# CNC-PowerSwitch-2016-v0_96.net
KiCad netlist of a schematic drawn in EAGLE
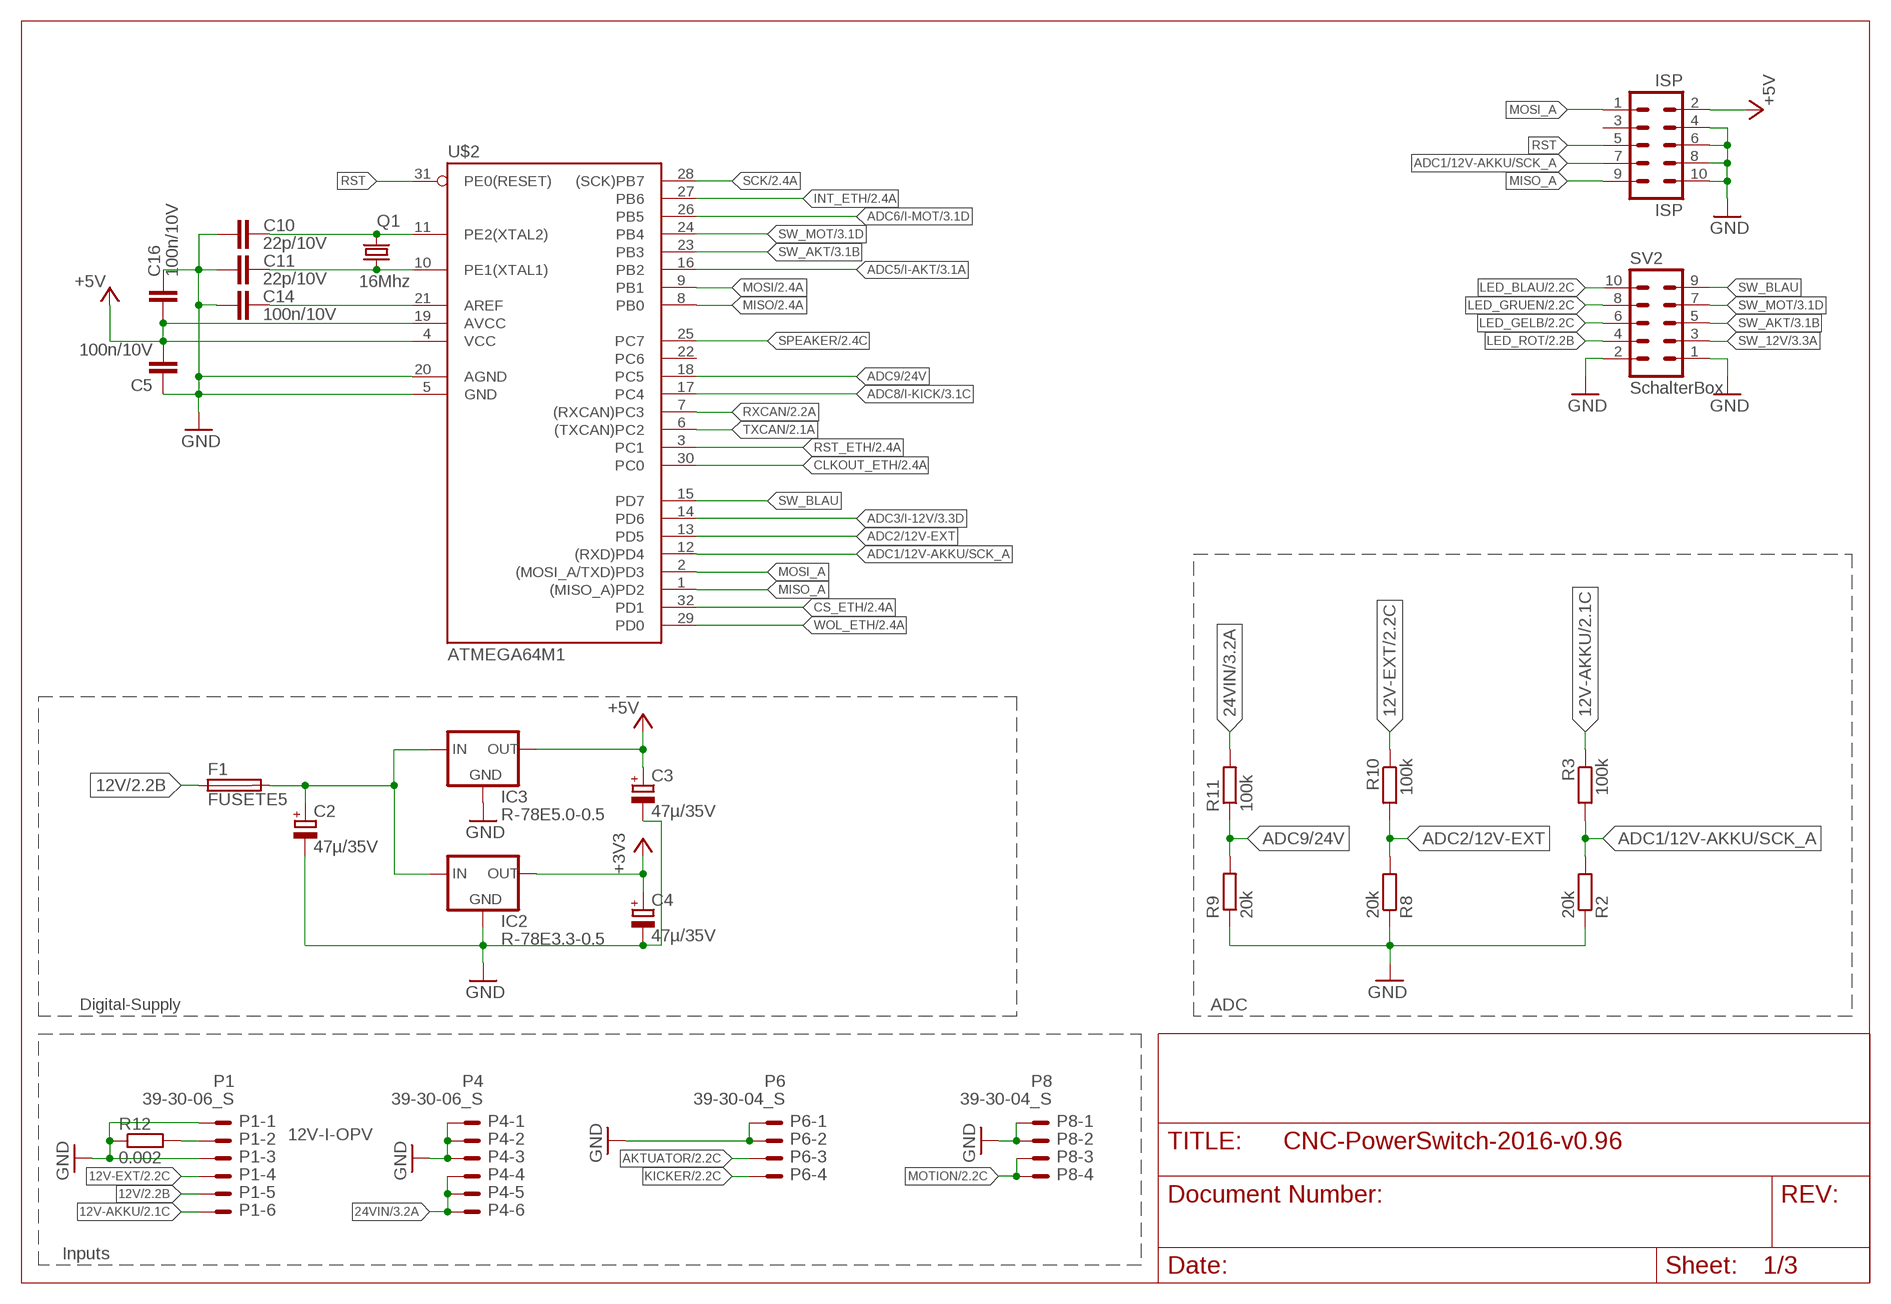
[diagram p0: schematic, sheet 1]
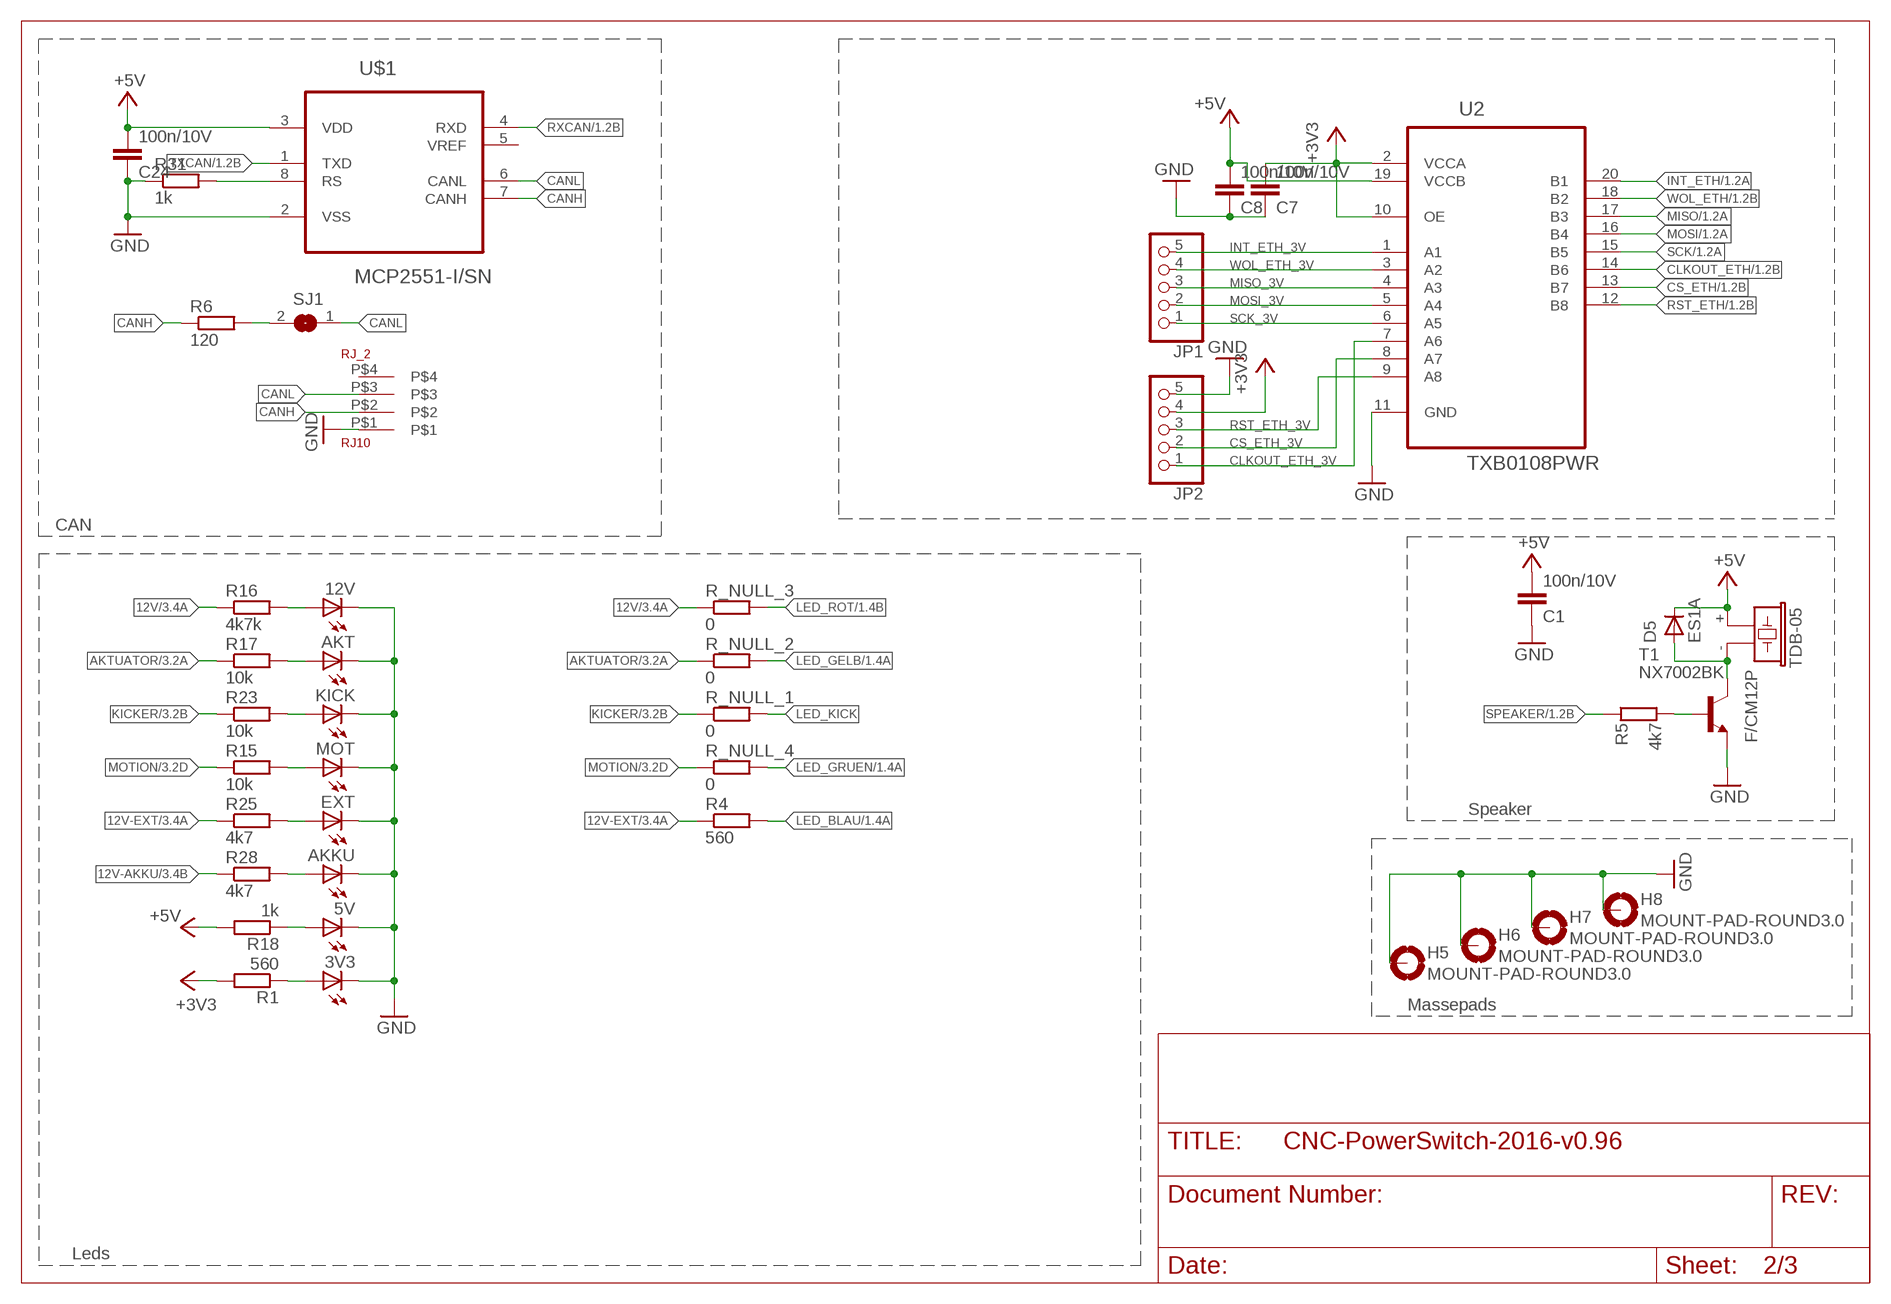
[diagram p1: schematic, sheet 2]
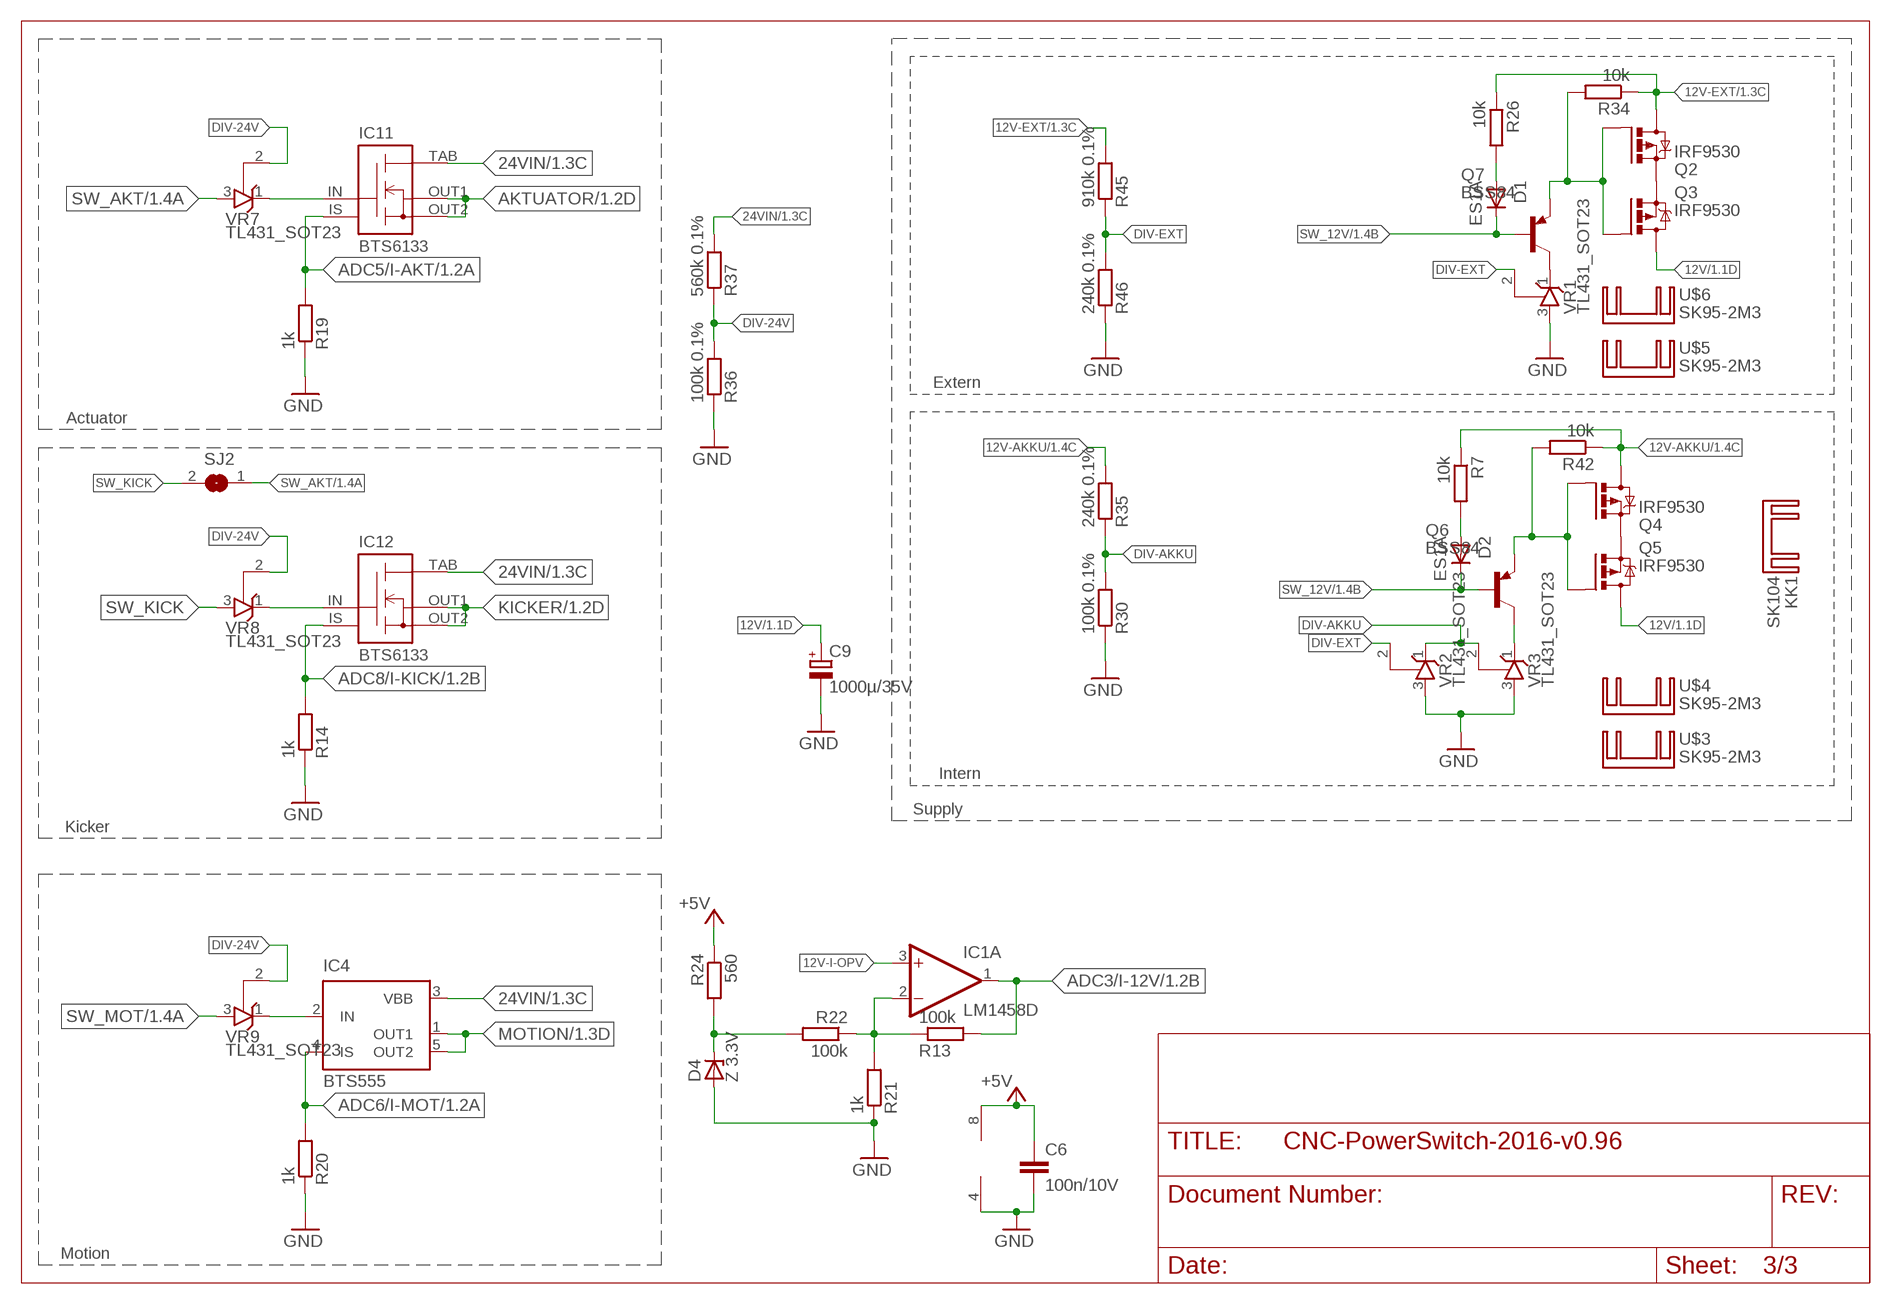
[diagram p2: schematic, sheet 3]

(export (version "E")
  (design (tool "Eeschema 10.0.6"))
  (components
    (comp (ref "C2")
      (value "47µ/35V")
      (footprint "eagle-import:PANASONIC_D")
      (libsource (lib "eagle-import") (part "CPOL-EUD"))
    )
    (comp (ref "C3")
      (value "47µ/35V")
      (footprint "eagle-import:PANASONIC_D")
      (libsource (lib "eagle-import") (part "CPOL-EUD"))
    )
    (comp (ref "C4")
      (value "47µ/35V")
      (footprint "eagle-import:PANASONIC_D")
      (libsource (lib "eagle-import") (part "CPOL-EUD"))
    )
    (comp (ref "C5")
      (value "100n/10V")
      (footprint "eagle-import:C0603")
      (libsource (lib "eagle-import") (part "C-EUC0603"))
    )
    (comp (ref "C10")
      (value "22p/10V")
      (footprint "eagle-import:C0603")
      (libsource (lib "eagle-import") (part "C-EUC0603"))
    )
    (comp (ref "C11")
      (value "22p/10V")
      (footprint "eagle-import:C0603")
      (libsource (lib "eagle-import") (part "C-EUC0603"))
    )
    (comp (ref "C14")
      (value "100n/10V")
      (footprint "eagle-import:C0603")
      (libsource (lib "eagle-import") (part "C-EUC0603"))
    )
    (comp (ref "C16")
      (value "100n/10V")
      (footprint "eagle-import:C0603")
      (libsource (lib "eagle-import") (part "C-EUC0603"))
    )
    (comp (ref "F1")
      (value "FUSETE5")
      (footprint "eagle-import:TE5")
      (libsource (lib "eagle-import") (part "FUSETE5"))
    )
    (comp (ref "IC2")
      (value "R-78E3.3-0.5")
      (footprint "eagle-import:SIP3")
      (fields (field (name "MF") "Recom") (field (name "MPN") "R-783.3-0.5"))
      (libsource (lib "eagle-import") (part "R-78E-0.53.3"))
    )
    (comp (ref "IC3")
      (value "R-78E5.0-0.5")
      (footprint "eagle-import:SIP3")
      (fields (field (name "MF") "Recom") (field (name "MPN") "R-785.0-0.5"))
      (libsource (lib "eagle-import") (part "R-78E-0.55.0"))
    )
    (comp (ref "ISP")
      (value "ISP")
      (footprint "eagle-import:ML10")
      (libsource (lib "eagle-import") (part "ML10"))
    )
    (comp (ref "P1")
      (value "39-30-06_S")
      (footprint "eagle-import:39-30-_06_")
      (libsource (lib "eagle-import") (part "39-30-?06?_S"))
    )
    (comp (ref "P4")
      (value "39-30-06_S")
      (footprint "eagle-import:39-30-_06_")
      (libsource (lib "eagle-import") (part "39-30-?06?_S"))
    )
    (comp (ref "P6")
      (value "39-30-04_S")
      (footprint "eagle-import:39-30-_04_")
      (libsource (lib "eagle-import") (part "39-30-?04?_S"))
    )
    (comp (ref "P8")
      (value "39-30-04_S")
      (footprint "eagle-import:39-30-_04_")
      (libsource (lib "eagle-import") (part "39-30-?04?_S"))
    )
    (comp (ref "Q1")
      (value "16Mhz")
      (footprint "eagle-import:HC49UP")
      (libsource (lib "eagle-import") (part "CRYSTALHC49UP"))
    )
    (comp (ref "R2")
      (value "20k")
      (footprint "eagle-import:R0805")
      (libsource (lib "eagle-import") (part "R-EU_R0805"))
    )
    (comp (ref "R3")
      (value "100k")
      (footprint "eagle-import:R0805")
      (libsource (lib "eagle-import") (part "R-EU_R0805"))
    )
    (comp (ref "R8")
      (value "20k")
      (footprint "eagle-import:R0805")
      (libsource (lib "eagle-import") (part "R-EU_R0805"))
    )
    (comp (ref "R9")
      (value "20k")
      (footprint "eagle-import:R0805")
      (libsource (lib "eagle-import") (part "R-EU_R0805"))
    )
    (comp (ref "R10")
      (value "100k")
      (footprint "eagle-import:R0805")
      (libsource (lib "eagle-import") (part "R-EU_R0805"))
    )
    (comp (ref "R11")
      (value "100k")
      (footprint "eagle-import:R0805")
      (libsource (lib "eagle-import") (part "R-EU_R0805"))
    )
    (comp (ref "R12")
      (value "0.002")
      (footprint "eagle-import:R2512")
      (libsource (lib "eagle-import") (part "R-EU_R2512"))
    )
    (comp (ref "SV2")
      (value "SchalterBox")
      (footprint "eagle-import:ML10L")
      (libsource (lib "eagle-import") (part "ML10L"))
    )
    (comp (ref "U$2")
      (value "ATMEGA64M1")
      (footprint "eagle-import:TQFP32-08")
      (libsource (lib "eagle-import") (part "ATMEGA64M1"))
    )
    (comp (ref "C6")
      (value "100n/10V")
      (footprint "eagle-import:C0603")
      (libsource (lib "eagle-import") (part "C-EUC0603"))
    )
    (comp (ref "C9")
      (value "1000µ/35V")
      (footprint "eagle-import:E5-10,5")
      (libsource (lib "eagle-import") (part "CPOL-EUE5-10.5"))
    )
    (comp (ref "D1")
      (value "ES1A")
      (footprint "eagle-import:SMA-DO214AC")
      (libsource (lib "eagle-import") (part "GF1"))
    )
    (comp (ref "D2")
      (value "ES1A")
      (footprint "eagle-import:SMA-DO214AC")
      (libsource (lib "eagle-import") (part "GF1"))
    )
    (comp (ref "D4")
      (value "Z 3.3V")
      (footprint "eagle-import:SOT23")
      (libsource (lib "eagle-import") (part "ZENER-DIODESOT23"))
    )
    (comp (ref "IC1")
      (value "LM1458D")
      (footprint "eagle-import:SO08")
      (libsource (lib "eagle-import") (part "1458DLM"))
    )
    (comp (ref "IC4")
      (value "BTS555")
      (footprint "eagle-import:TO220-51")
      (fields (field (name "MF") "FARNELL") (field (name "MPN") "BTS555."))
      (libsource (lib "eagle-import") (part "BTS555"))
    )
    (comp (ref "IC11")
      (value "BTS6133")
      (footprint "eagle-import:TO252-51")
      (libsource (lib "eagle-import") (part "BTS6133"))
    )
    (comp (ref "IC12")
      (value "BTS6133")
      (footprint "eagle-import:TO252-51")
      (libsource (lib "eagle-import") (part "BTS6133"))
    )
    (comp (ref "KK1")
      (value "SK104")
      (footprint "eagle-import:SK104")
      (libsource (lib "eagle-import") (part "SK104"))
    )
    (comp (ref "Q2")
      (value "IRF9530")
      (footprint "eagle-import:TO220BV")
      (libsource (lib "eagle-import") (part "IRF9530"))
    )
    (comp (ref "Q3")
      (value "IRF9530")
      (footprint "eagle-import:TO220BV")
      (libsource (lib "eagle-import") (part "IRF9530"))
    )
    (comp (ref "Q4")
      (value "IRF9530")
      (footprint "eagle-import:TO220BV")
      (libsource (lib "eagle-import") (part "IRF9530"))
    )
    (comp (ref "Q5")
      (value "IRF9530")
      (footprint "eagle-import:TO220BV")
      (libsource (lib "eagle-import") (part "IRF9530"))
    )
    (comp (ref "Q6")
      (value "BSS84")
      (footprint "eagle-import:SOT23-BEC")
      (libsource (lib "eagle-import") (part "BC858SMDALT1"))
    )
    (comp (ref "Q7")
      (value "BSS84")
      (footprint "eagle-import:SOT23-BEC")
      (libsource (lib "eagle-import") (part "BC858SMDALT1"))
    )
    (comp (ref "R7")
      (value "10k")
      (footprint "eagle-import:R0805")
      (libsource (lib "eagle-import") (part "R-EU_R0805"))
    )
    (comp (ref "R13")
      (value "100k")
      (footprint "eagle-import:R0805")
      (libsource (lib "eagle-import") (part "R-EU_R0805"))
    )
    (comp (ref "R14")
      (value "1k")
      (footprint "eagle-import:R0805")
      (libsource (lib "eagle-import") (part "R-EU_R0805"))
    )
    (comp (ref "R19")
      (value "1k")
      (footprint "eagle-import:R0805")
      (libsource (lib "eagle-import") (part "R-EU_R0805"))
    )
    (comp (ref "R20")
      (value "1k")
      (footprint "eagle-import:R0805")
      (libsource (lib "eagle-import") (part "R-EU_R0805"))
    )
    (comp (ref "R21")
      (value "1k")
      (footprint "eagle-import:R0805")
      (libsource (lib "eagle-import") (part "R-EU_R0805"))
    )
    (comp (ref "R22")
      (value "100k")
      (footprint "eagle-import:R0805")
      (libsource (lib "eagle-import") (part "R-EU_R0805"))
    )
    (comp (ref "R24")
      (value "560")
      (footprint "eagle-import:R0805")
      (libsource (lib "eagle-import") (part "R-EU_R0805"))
    )
    (comp (ref "R26")
      (value "10k")
      (footprint "eagle-import:R0805")
      (libsource (lib "eagle-import") (part "R-EU_R0805"))
    )
    (comp (ref "R30")
      (value "100k 0.1%")
      (footprint "eagle-import:R0805")
      (libsource (lib "eagle-import") (part "R-EU_R0805"))
    )
    (comp (ref "R34")
      (value "10k")
      (footprint "eagle-import:R0805")
      (libsource (lib "eagle-import") (part "R-EU_R0805"))
    )
    (comp (ref "R35")
      (value "240k 0.1%")
      (footprint "eagle-import:R0805")
      (libsource (lib "eagle-import") (part "R-EU_R0805"))
    )
    (comp (ref "R36")
      (value "100k 0.1%")
      (footprint "eagle-import:R0805")
      (libsource (lib "eagle-import") (part "R-EU_R0805"))
    )
    (comp (ref "R37")
      (value "560k 0.1%")
      (footprint "eagle-import:R0805")
      (libsource (lib "eagle-import") (part "R-EU_R0805"))
    )
    (comp (ref "R42")
      (value "10k")
      (footprint "eagle-import:R0805")
      (libsource (lib "eagle-import") (part "R-EU_R0805"))
    )
    (comp (ref "R45")
      (value "910k 0.1%")
      (footprint "eagle-import:R0805")
      (libsource (lib "eagle-import") (part "R-EU_R0805"))
    )
    (comp (ref "R46")
      (value "240k 0.1%")
      (footprint "eagle-import:R0805")
      (libsource (lib "eagle-import") (part "R-EU_R0805"))
    )
    (comp (ref "SJ2") (value "SJ") (footprint "eagle-import:SJ") (libsource (lib "eagle-import") (part "SJ")))
    (comp (ref "U$3")
      (value "SK95-2M3")
      (footprint "eagle-import:SK95-2M3")
      (libsource (lib "eagle-import") (part "SK95-2M3"))
    )
    (comp (ref "U$4")
      (value "SK95-2M3")
      (footprint "eagle-import:SK95-2M3")
      (libsource (lib "eagle-import") (part "SK95-2M3"))
    )
    (comp (ref "U$5")
      (value "SK95-2M3")
      (footprint "eagle-import:SK95-2M3")
      (libsource (lib "eagle-import") (part "SK95-2M3"))
    )
    (comp (ref "U$6")
      (value "SK95-2M3")
      (footprint "eagle-import:SK95-2M3")
      (libsource (lib "eagle-import") (part "SK95-2M3"))
    )
    (comp (ref "VR1")
      (value "TL431_SOT23")
      (footprint "eagle-import:SOT23")
      (libsource (lib "eagle-import") (part "TL431_SOT23"))
    )
    (comp (ref "VR2")
      (value "TL431_SOT23")
      (footprint "eagle-import:SOT23")
      (libsource (lib "eagle-import") (part "TL431_SOT23"))
    )
    (comp (ref "VR3")
      (value "TL431_SOT23")
      (footprint "eagle-import:SOT23")
      (libsource (lib "eagle-import") (part "TL431_SOT23"))
    )
    (comp (ref "VR7")
      (value "TL431_SOT23")
      (footprint "eagle-import:SOT23")
      (libsource (lib "eagle-import") (part "TL431_SOT23"))
    )
    (comp (ref "VR8")
      (value "TL431_SOT23")
      (footprint "eagle-import:SOT23")
      (libsource (lib "eagle-import") (part "TL431_SOT23"))
    )
    (comp (ref "VR9")
      (value "TL431_SOT23")
      (footprint "eagle-import:SOT23")
      (libsource (lib "eagle-import") (part "TL431_SOT23"))
    )
    (comp (ref "3V3")
      (value "LEDCHIPLED_0805")
      (footprint "eagle-import:CHIPLED_0805")
      (libsource (lib "eagle-import") (part "LEDCHIPLED_0805"))
    )
    (comp (ref "5V")
      (value "LEDCHIPLED_0805")
      (footprint "eagle-import:CHIPLED_0805")
      (libsource (lib "eagle-import") (part "LEDCHIPLED_0805"))
    )
    (comp (ref "12V")
      (value "LEDCHIPLED_0805")
      (footprint "eagle-import:CHIPLED_0805")
      (libsource (lib "eagle-import") (part "LEDCHIPLED_0805"))
    )
    (comp (ref "AKKU")
      (value "LEDCHIPLED_0805")
      (footprint "eagle-import:CHIPLED_0805")
      (libsource (lib "eagle-import") (part "LEDCHIPLED_0805"))
    )
    (comp (ref "AKT")
      (value "LEDCHIPLED_0805")
      (footprint "eagle-import:CHIPLED_0805")
      (libsource (lib "eagle-import") (part "LEDCHIPLED_0805"))
    )
    (comp (ref "C1")
      (value "100n/10V")
      (footprint "eagle-import:C0603")
      (libsource (lib "eagle-import") (part "C-EUC0603"))
    )
    (comp (ref "C7")
      (value "100n/10V")
      (footprint "eagle-import:C0603")
      (libsource (lib "eagle-import") (part "C-EUC0603"))
    )
    (comp (ref "C8")
      (value "100n/10V")
      (footprint "eagle-import:C0603")
      (libsource (lib "eagle-import") (part "C-EUC0603"))
    )
    (comp (ref "C24")
      (value "100n/10V")
      (footprint "eagle-import:C0603")
      (libsource (lib "eagle-import") (part "C-EUC0603"))
    )
    (comp (ref "D5")
      (value "ES1A")
      (footprint "eagle-import:SMA-DO214AC")
      (libsource (lib "eagle-import") (part "GF1"))
    )
    (comp (ref "EXT")
      (value "LEDCHIPLED_0805")
      (footprint "eagle-import:CHIPLED_0805")
      (libsource (lib "eagle-import") (part "LEDCHIPLED_0805"))
    )
    (comp (ref "H5")
      (value "MOUNT-PAD-ROUND3.0")
      (footprint "eagle-import:3,0-PAD")
      (libsource (lib "eagle-import") (part "MOUNT-PAD-ROUND3.0"))
    )
    (comp (ref "H6")
      (value "MOUNT-PAD-ROUND3.0")
      (footprint "eagle-import:3,0-PAD")
      (libsource (lib "eagle-import") (part "MOUNT-PAD-ROUND3.0"))
    )
    (comp (ref "H7")
      (value "MOUNT-PAD-ROUND3.0")
      (footprint "eagle-import:3,0-PAD")
      (libsource (lib "eagle-import") (part "MOUNT-PAD-ROUND3.0"))
    )
    (comp (ref "H8")
      (value "MOUNT-PAD-ROUND3.0")
      (footprint "eagle-import:3,0-PAD")
      (libsource (lib "eagle-import") (part "MOUNT-PAD-ROUND3.0"))
    )
    (comp (ref "JP1")
      (value "PINHD-1X5")
      (footprint "eagle-import:1X05")
      (libsource (lib "eagle-import") (part "PINHD-1X5"))
    )
    (comp (ref "JP2")
      (value "PINHD-1X5")
      (footprint "eagle-import:1X05")
      (libsource (lib "eagle-import") (part "PINHD-1X5"))
    )
    (comp (ref "KICK")
      (value "LEDCHIPLED_0805")
      (footprint "eagle-import:CHIPLED_0805")
      (libsource (lib "eagle-import") (part "LEDCHIPLED_0805"))
    )
    (comp (ref "MOT")
      (value "LEDCHIPLED_0805")
      (footprint "eagle-import:CHIPLED_0805")
      (libsource (lib "eagle-import") (part "LEDCHIPLED_0805"))
    )
    (comp (ref "R1")
      (value "560")
      (footprint "eagle-import:R0805")
      (libsource (lib "eagle-import") (part "R-EU_R0805"))
    )
    (comp (ref "R4")
      (value "560")
      (footprint "eagle-import:R0805")
      (libsource (lib "eagle-import") (part "R-EU_R0805"))
    )
    (comp (ref "R5")
      (value "4k7")
      (footprint "eagle-import:R0805")
      (libsource (lib "eagle-import") (part "R-EU_R0805"))
    )
    (comp (ref "R6")
      (value "120")
      (footprint "eagle-import:M0805")
      (libsource (lib "eagle-import") (part "R-EU_M0805"))
    )
    (comp (ref "R15")
      (value "10k")
      (footprint "eagle-import:R0805")
      (libsource (lib "eagle-import") (part "R-EU_R0805"))
    )
    (comp (ref "R16")
      (value "4k7k")
      (footprint "eagle-import:R0805")
      (libsource (lib "eagle-import") (part "R-EU_R0805"))
    )
    (comp (ref "R17")
      (value "10k")
      (footprint "eagle-import:R0805")
      (libsource (lib "eagle-import") (part "R-EU_R0805"))
    )
    (comp (ref "R18")
      (value "1k")
      (footprint "eagle-import:R0805")
      (libsource (lib "eagle-import") (part "R-EU_R0805"))
    )
    (comp (ref "R23")
      (value "10k")
      (footprint "eagle-import:R0805")
      (libsource (lib "eagle-import") (part "R-EU_R0805"))
    )
    (comp (ref "R25")
      (value "4k7")
      (footprint "eagle-import:R0805")
      (libsource (lib "eagle-import") (part "R-EU_R0805"))
    )
    (comp (ref "R28")
      (value "4k7")
      (footprint "eagle-import:R0805")
      (libsource (lib "eagle-import") (part "R-EU_R0805"))
    )
    (comp (ref "R31")
      (value "1k")
      (footprint "eagle-import:R0805")
      (libsource (lib "eagle-import") (part "R-EU_R0805"))
    )
    (comp (ref "RJ_2")
      (value "RJ10")
      (footprint "eagle-import:RJ10")
      (libsource (lib "eagle-import") (part "RJ10"))
    )
    (comp (ref "R_NULL_1")
      (value "0")
      (footprint "eagle-import:R0402")
      (libsource (lib "eagle-import") (part "R-EU_R0402"))
    )
    (comp (ref "R_NULL_2")
      (value "0")
      (footprint "eagle-import:R0402")
      (libsource (lib "eagle-import") (part "R-EU_R0402"))
    )
    (comp (ref "R_NULL_3")
      (value "0")
      (footprint "eagle-import:R0402")
      (libsource (lib "eagle-import") (part "R-EU_R0402"))
    )
    (comp (ref "R_NULL_4")
      (value "0")
      (footprint "eagle-import:R0402")
      (libsource (lib "eagle-import") (part "R-EU_R0402"))
    )
    (comp (ref "SJ1") (value "SJ") (footprint "eagle-import:SJ") (libsource (lib "eagle-import") (part "SJ")))
    (comp (ref "T1")
      (value "NX7002BK")
      (footprint "eagle-import:SOT23")
      (libsource (lib "eagle-import") (part "BC849"))
    )
    (comp (ref "TDB-05")
      (value "F/CM12P")
      (footprint "eagle-import:F_CM12P")
      (libsource (lib "eagle-import") (part "F/CM12P"))
    )
    (comp (ref "U$1")
      (value "MCP2551-I/SN")
      (footprint "eagle-import:SOIC127P600X175-8N")
      (libsource (lib "eagle-import") (part "MCP2551-I/SN"))
    )
    (comp (ref "U2")
      (value "TXB0108PWR")
      (footprint "eagle-import:SOP65P640X120-20N")
      (libsource (lib "eagle-import") (part "TXB0108PWR"))
    )
  )
  (nets
    (net (code "1") (name "+3V3") (class "Default")
      (node (ref "C4") (pin "+") (pinfunction "+_+") (pintype "passive"))
      (node (ref "C7") (pin "2") (pinfunction "2_2") (pintype "passive"))
      (node (ref "IC2") (pin "3") (pinfunction "OUT_3") (pintype "passive"))
      (node (ref "JP2") (pin "4") (pinfunction "4_4") (pintype "passive"))
      (node (ref "R1") (pin "2") (pinfunction "2_2") (pintype "passive"))
      (node (ref "U2") (pin "10") (pinfunction "OE_10") (pintype "input"))
      (node (ref "U2") (pin "2") (pinfunction "VCCA_2") (pintype "power_in"))
    )
    (net (code "2") (name "+5V") (class "Default")
      (node (ref "C1") (pin "2") (pinfunction "2_2") (pintype "passive"))
      (node (ref "C16") (pin "1") (pinfunction "1_1") (pintype "passive"))
      (node (ref "C24") (pin "2") (pinfunction "2_2") (pintype "passive"))
      (node (ref "C3") (pin "+") (pinfunction "+_+") (pintype "passive"))
      (node (ref "C5") (pin "2") (pinfunction "2_2") (pintype "passive"))
      (node (ref "C6") (pin "1") (pinfunction "1_1") (pintype "passive"))
      (node (ref "C8") (pin "2") (pinfunction "2_2") (pintype "passive"))
      (node (ref "D5") (pin "K") (pinfunction "C_K") (pintype "passive"))
      (node (ref "IC1") (pin "8") (pinfunction "V+_8") (pintype "power_in"))
      (node (ref "IC3") (pin "3") (pinfunction "OUT_3") (pintype "passive"))
      (node (ref "ISP") (pin "2") (pinfunction "2_2") (pintype "passive"))
      (node (ref "R18") (pin "2") (pinfunction "2_2") (pintype "passive"))
      (node (ref "R24") (pin "1") (pinfunction "1_1") (pintype "passive"))
      (node (ref "TDB-05") (pin "+") (pinfunction "1_+") (pintype "passive"))
      (node (ref "U$1") (pin "3") (pinfunction "VDD_3") (pintype "power_in"))
      (node (ref "U$2") (pin "19") (pinfunction "AVCC_19") (pintype "bidirectional"))
      (node (ref "U$2") (pin "4") (pinfunction "VCC_4") (pintype "bidirectional"))
      (node (ref "U2") (pin "19") (pinfunction "VCCB_19") (pintype "power_in"))
    )
    (net (code "3") (name "12V") (class "Default")
      (node (ref "C9") (pin "+") (pinfunction "+_+") (pintype "passive"))
      (node (ref "F1") (pin "1") (pinfunction "1_1") (pintype "passive"))
      (node (ref "P1") (pin "5") (pinfunction "P_5") (pintype "passive"))
      (node (ref "Q3") (pin "D") (pinfunction "D_D") (pintype "passive"))
      (node (ref "Q5") (pin "D") (pinfunction "D_D") (pintype "passive"))
      (node (ref "R16") (pin "1") (pinfunction "1_1") (pintype "passive"))
      (node (ref "R_NULL_3") (pin "1") (pinfunction "1_1") (pintype "passive"))
    )
    (net (code "4") (name "12V-AKKU") (class "Default")
      (node (ref "P1") (pin "6") (pinfunction "P_6") (pintype "passive"))
      (node (ref "Q4") (pin "D") (pinfunction "D_D") (pintype "passive"))
      (node (ref "R28") (pin "1") (pinfunction "1_1") (pintype "passive"))
      (node (ref "R3") (pin "1") (pinfunction "1_1") (pintype "passive"))
      (node (ref "R35") (pin "2") (pinfunction "2_2") (pintype "passive"))
      (node (ref "R42") (pin "1") (pinfunction "1_1") (pintype "passive"))
      (node (ref "R7") (pin "1") (pinfunction "1_1") (pintype "passive"))
    )
    (net (code "5") (name "12V-EXT") (class "Default")
      (node (ref "P1") (pin "4") (pinfunction "P_4") (pintype "passive"))
      (node (ref "Q2") (pin "D") (pinfunction "D_D") (pintype "passive"))
      (node (ref "R10") (pin "1") (pinfunction "1_1") (pintype "passive"))
      (node (ref "R25") (pin "1") (pinfunction "1_1") (pintype "passive"))
      (node (ref "R26") (pin "1") (pinfunction "1_1") (pintype "passive"))
      (node (ref "R34") (pin "1") (pinfunction "1_1") (pintype "passive"))
      (node (ref "R4") (pin "1") (pinfunction "1_1") (pintype "passive"))
      (node (ref "R45") (pin "2") (pinfunction "2_2") (pintype "passive"))
    )
    (net (code "6") (name "12V-I-OPV") (class "Default")
      (node (ref "IC1") (pin "3") (pinfunction "+IN_3") (pintype "input"))
      (node (ref "P1") (pin "2") (pinfunction "P_2") (pintype "passive"))
      (node (ref "R12") (pin "2") (pinfunction "2_2") (pintype "passive"))
    )
    (net (code "7") (name "24VIN") (class "Default")
      (node (ref "IC11") (pin "TAB") (pinfunction "VBB_TAB") (pintype "power_in"))
      (node (ref "IC12") (pin "TAB") (pinfunction "VBB_TAB") (pintype "power_in"))
      (node (ref "IC4") (pin "3") (pinfunction "VBB_3") (pintype "passive"))
      (node (ref "P4") (pin "4") (pinfunction "P_4") (pintype "passive"))
      (node (ref "P4") (pin "5") (pinfunction "P_5") (pintype "passive"))
      (node (ref "P4") (pin "6") (pinfunction "P_6") (pintype "passive"))
      (node (ref "R11") (pin "2") (pinfunction "2_2") (pintype "passive"))
      (node (ref "R37") (pin "2") (pinfunction "2_2") (pintype "passive"))
    )
    (net (code "8") (name "ADC1{slash}12V-AKKU{slash}SCK_A") (class "Default")
      (node (ref "ISP") (pin "7") (pinfunction "7_7") (pintype "passive"))
      (node (ref "R2") (pin "2") (pinfunction "2_2") (pintype "passive"))
      (node (ref "R3") (pin "2") (pinfunction "2_2") (pintype "passive"))
      (node (ref "U$2") (pin "12") (pinfunction "(RXD)PD4_12") (pintype "bidirectional"))
    )
    (net (code "9") (name "ADC2{slash}12V-EXT") (class "Default")
      (node (ref "R10") (pin "2") (pinfunction "2_2") (pintype "passive"))
      (node (ref "R8") (pin "2") (pinfunction "2_2") (pintype "passive"))
      (node (ref "U$2") (pin "13") (pinfunction "PD5_13") (pintype "bidirectional"))
    )
    (net (code "10") (name "ADC3{slash}I-12V") (class "Default")
      (node (ref "IC1") (pin "1") (pinfunction "OUT_1") (pintype "output"))
      (node (ref "R13") (pin "2") (pinfunction "2_2") (pintype "passive"))
      (node (ref "U$2") (pin "14") (pinfunction "PD6_14") (pintype "bidirectional"))
    )
    (net (code "11") (name "ADC5{slash}I-AKT") (class "Default")
      (node (ref "IC11") (pin "IS") (pinfunction "IS_IS") (pintype "passive"))
      (node (ref "R19") (pin "2") (pinfunction "2_2") (pintype "passive"))
      (node (ref "U$2") (pin "16") (pinfunction "PB2_16") (pintype "bidirectional"))
    )
    (net (code "12") (name "ADC6{slash}I-MOT") (class "Default")
      (node (ref "IC4") (pin "4") (pinfunction "IS_4") (pintype "passive"))
      (node (ref "R20") (pin "2") (pinfunction "2_2") (pintype "passive"))
      (node (ref "U$2") (pin "26") (pinfunction "PB5_26") (pintype "bidirectional"))
    )
    (net (code "13") (name "ADC8{slash}I-KICK") (class "Default")
      (node (ref "IC12") (pin "IS") (pinfunction "IS_IS") (pintype "passive"))
      (node (ref "R14") (pin "2") (pinfunction "2_2") (pintype "passive"))
      (node (ref "U$2") (pin "17") (pinfunction "PC4_17") (pintype "bidirectional"))
    )
    (net (code "14") (name "ADC9{slash}24V") (class "Default")
      (node (ref "R11") (pin "1") (pinfunction "1_1") (pintype "passive"))
      (node (ref "R9") (pin "2") (pinfunction "2_2") (pintype "passive"))
      (node (ref "U$2") (pin "18") (pinfunction "PC5_18") (pintype "bidirectional"))
    )
    (net (code "15") (name "AKTUATOR") (class "Default")
      (node (ref "IC11") (pin "OUT1") (pinfunction "OUT_OUT1") (pintype "passive"))
      (node (ref "IC11") (pin "OUT2") (pinfunction "OUT_OUT2") (pintype "passive"))
      (node (ref "P6") (pin "3") (pinfunction "P_3") (pintype "passive"))
      (node (ref "R17") (pin "1") (pinfunction "1_1") (pintype "passive"))
      (node (ref "R_NULL_2") (pin "1") (pinfunction "1_1") (pintype "passive"))
    )
    (net (code "16") (name "CANH") (class "Default")
      (node (ref "R6") (pin "1") (pinfunction "1_1") (pintype "passive"))
      (node (ref "RJ_2") (pin "P$2") (pinfunction "P$2_P$2") (pintype "bidirectional"))
      (node (ref "U$1") (pin "7") (pinfunction "CANH_7") (pintype "bidirectional"))
    )
    (net (code "17") (name "CANL") (class "Default")
      (node (ref "RJ_2") (pin "P$3") (pinfunction "P$3_P$3") (pintype "bidirectional"))
      (node (ref "SJ1") (pin "1") (pinfunction "1_1") (pintype "passive"))
      (node (ref "U$1") (pin "6") (pinfunction "CANL_6") (pintype "bidirectional"))
    )
    (net (code "18") (name "CLKOUT_ETH") (class "Default")
      (node (ref "U$2") (pin "30") (pinfunction "PC0_30") (pintype "bidirectional"))
      (node (ref "U2") (pin "14") (pinfunction "B6_14") (pintype "bidirectional"))
    )
    (net (code "19") (name "CLKOUT_ETH_3V") (class "Default")
      (node (ref "JP2") (pin "1") (pinfunction "1_1") (pintype "passive"))
      (node (ref "U2") (pin "7") (pinfunction "A6_7") (pintype "bidirectional"))
    )
    (net (code "20") (name "CS_ETH") (class "Default")
      (node (ref "U$2") (pin "32") (pinfunction "PD1_32") (pintype "bidirectional"))
      (node (ref "U2") (pin "13") (pinfunction "B7_13") (pintype "bidirectional"))
    )
    (net (code "21") (name "CS_ETH_3V") (class "Default")
      (node (ref "JP2") (pin "2") (pinfunction "2_2") (pintype "passive"))
      (node (ref "U2") (pin "8") (pinfunction "A7_8") (pintype "bidirectional"))
    )
    (net (code "22") (name "DIV-24V") (class "Default")
      (node (ref "R36") (pin "2") (pinfunction "2_2") (pintype "passive"))
      (node (ref "R37") (pin "1") (pinfunction "1_1") (pintype "passive"))
      (node (ref "VR7") (pin "2") (pinfunction "R_2") (pintype "passive"))
      (node (ref "VR8") (pin "2") (pinfunction "R_2") (pintype "passive"))
      (node (ref "VR9") (pin "2") (pinfunction "R_2") (pintype "passive"))
    )
    (net (code "23") (name "DIV-AKKU") (class "Default")
      (node (ref "R30") (pin "2") (pinfunction "2_2") (pintype "passive"))
      (node (ref "R35") (pin "1") (pinfunction "1_1") (pintype "passive"))
      (node (ref "VR2") (pin "1") (pinfunction "C_1") (pintype "passive"))
      (node (ref "VR3") (pin "2") (pinfunction "R_2") (pintype "passive"))
    )
    (net (code "24") (name "DIV-EXT") (class "Default")
      (node (ref "R45") (pin "1") (pinfunction "1_1") (pintype "passive"))
      (node (ref "R46") (pin "2") (pinfunction "2_2") (pintype "passive"))
      (node (ref "VR1") (pin "2") (pinfunction "R_2") (pintype "passive"))
      (node (ref "VR2") (pin "2") (pinfunction "R_2") (pintype "passive"))
    )
    (net (code "25") (name "GND") (class "Default")
      (node (ref "12V") (pin "C") (pinfunction "C_C") (pintype "passive"))
      (node (ref "3V3") (pin "C") (pinfunction "C_C") (pintype "passive"))
      (node (ref "5V") (pin "C") (pinfunction "C_C") (pintype "passive"))
      (node (ref "AKKU") (pin "C") (pinfunction "C_C") (pintype "passive"))
      (node (ref "AKT") (pin "C") (pinfunction "C_C") (pintype "passive"))
      (node (ref "C1") (pin "1") (pinfunction "1_1") (pintype "passive"))
      (node (ref "C10") (pin "1") (pinfunction "1_1") (pintype "passive"))
      (node (ref "C11") (pin "1") (pinfunction "1_1") (pintype "passive"))
      (node (ref "C14") (pin "1") (pinfunction "1_1") (pintype "passive"))
      (node (ref "C16") (pin "2") (pinfunction "2_2") (pintype "passive"))
      (node (ref "C2") (pin "-") (pinfunction "-_-") (pintype "passive"))
      (node (ref "C24") (pin "1") (pinfunction "1_1") (pintype "passive"))
      (node (ref "C3") (pin "-") (pinfunction "-_-") (pintype "passive"))
      (node (ref "C4") (pin "-") (pinfunction "-_-") (pintype "passive"))
      (node (ref "C5") (pin "1") (pinfunction "1_1") (pintype "passive"))
      (node (ref "C6") (pin "2") (pinfunction "2_2") (pintype "passive"))
      (node (ref "C7") (pin "1") (pinfunction "1_1") (pintype "passive"))
      (node (ref "C8") (pin "1") (pinfunction "1_1") (pintype "passive"))
      (node (ref "C9") (pin "-") (pinfunction "-_-") (pintype "passive"))
      (node (ref "D4") (pin "1") (pinfunction "A_1") (pintype "passive"))
      (node (ref "EXT") (pin "C") (pinfunction "C_C") (pintype "passive"))
      (node (ref "H5") (pin "B3,0") (pinfunction "MOUNT_B3,0") (pintype "passive"))
      (node (ref "H6") (pin "B3,0") (pinfunction "MOUNT_B3,0") (pintype "passive"))
      (node (ref "H7") (pin "B3,0") (pinfunction "MOUNT_B3,0") (pintype "passive"))
      (node (ref "H8") (pin "B3,0") (pinfunction "MOUNT_B3,0") (pintype "passive"))
      (node (ref "IC1") (pin "4") (pinfunction "V-_4") (pintype "power_in"))
      (node (ref "IC2") (pin "2") (pinfunction "GND_2") (pintype "input"))
      (node (ref "IC3") (pin "2") (pinfunction "GND_2") (pintype "input"))
      (node (ref "ISP") (pin "10") (pinfunction "10_10") (pintype "passive"))
      (node (ref "ISP") (pin "4") (pinfunction "4_4") (pintype "passive"))
      (node (ref "ISP") (pin "6") (pinfunction "6_6") (pintype "passive"))
      (node (ref "ISP") (pin "8") (pinfunction "8_8") (pintype "passive"))
      (node (ref "JP2") (pin "5") (pinfunction "5_5") (pintype "passive"))
      (node (ref "KICK") (pin "C") (pinfunction "C_C") (pintype "passive"))
      (node (ref "MOT") (pin "C") (pinfunction "C_C") (pintype "passive"))
      (node (ref "P1") (pin "1") (pinfunction "P_1") (pintype "passive"))
      (node (ref "P1") (pin "3") (pinfunction "P_3") (pintype "passive"))
      (node (ref "P4") (pin "1") (pinfunction "P_1") (pintype "passive"))
      (node (ref "P4") (pin "2") (pinfunction "P_2") (pintype "passive"))
      (node (ref "P4") (pin "3") (pinfunction "P_3") (pintype "passive"))
      (node (ref "P6") (pin "1") (pinfunction "P_1") (pintype "passive"))
      (node (ref "P6") (pin "2") (pinfunction "P_2") (pintype "passive"))
      (node (ref "P8") (pin "1") (pinfunction "P_1") (pintype "passive"))
      (node (ref "P8") (pin "2") (pinfunction "P_2") (pintype "passive"))
      (node (ref "R12") (pin "1") (pinfunction "1_1") (pintype "passive"))
      (node (ref "R14") (pin "1") (pinfunction "1_1") (pintype "passive"))
      (node (ref "R19") (pin "1") (pinfunction "1_1") (pintype "passive"))
      (node (ref "R2") (pin "1") (pinfunction "1_1") (pintype "passive"))
      (node (ref "R20") (pin "1") (pinfunction "1_1") (pintype "passive"))
      (node (ref "R21") (pin "1") (pinfunction "1_1") (pintype "passive"))
      (node (ref "R30") (pin "1") (pinfunction "1_1") (pintype "passive"))
      (node (ref "R31") (pin "1") (pinfunction "1_1") (pintype "passive"))
      (node (ref "R36") (pin "1") (pinfunction "1_1") (pintype "passive"))
      (node (ref "R46") (pin "1") (pinfunction "1_1") (pintype "passive"))
      (node (ref "R8") (pin "1") (pinfunction "1_1") (pintype "passive"))
      (node (ref "R9") (pin "1") (pinfunction "1_1") (pintype "passive"))
      (node (ref "RJ_2") (pin "P$1") (pinfunction "P$1_P$1") (pintype "bidirectional"))
      (node (ref "SV2") (pin "1") (pinfunction "1_1") (pintype "passive"))
      (node (ref "SV2") (pin "2") (pinfunction "2_2") (pintype "passive"))
      (node (ref "T1") (pin "2") (pinfunction "E_2") (pintype "passive"))
      (node (ref "U$1") (pin "2") (pinfunction "VSS_2") (pintype "passive"))
      (node (ref "U$2") (pin "20") (pinfunction "AGND_20") (pintype "power_in"))
      (node (ref "U$2") (pin "5") (pinfunction "GND_5") (pintype "power_in"))
      (node (ref "U2") (pin "11") (pinfunction "GND_11") (pintype "passive"))
      (node (ref "VR1") (pin "3") (pinfunction "A_3") (pintype "passive"))
      (node (ref "VR2") (pin "3") (pinfunction "A_3") (pintype "passive"))
      (node (ref "VR3") (pin "3") (pinfunction "A_3") (pintype "passive"))
    )
    (net (code "26") (name "INT_ETH") (class "Default")
      (node (ref "U$2") (pin "27") (pinfunction "PB6_27") (pintype "bidirectional"))
      (node (ref "U2") (pin "20") (pinfunction "B1_20") (pintype "bidirectional"))
    )
    (net (code "27") (name "INT_ETH_3V") (class "Default")
      (node (ref "JP1") (pin "5") (pinfunction "5_5") (pintype "passive"))
      (node (ref "U2") (pin "1") (pinfunction "A1_1") (pintype "bidirectional"))
    )
    (net (code "28") (name "KICKER") (class "Default")
      (node (ref "IC12") (pin "OUT1") (pinfunction "OUT_OUT1") (pintype "passive"))
      (node (ref "IC12") (pin "OUT2") (pinfunction "OUT_OUT2") (pintype "passive"))
      (node (ref "P6") (pin "4") (pinfunction "P_4") (pintype "passive"))
      (node (ref "R23") (pin "1") (pinfunction "1_1") (pintype "passive"))
      (node (ref "R_NULL_1") (pin "1") (pinfunction "1_1") (pintype "passive"))
    )
    (net (code "29") (name "LED_BLAU") (class "Default")
      (node (ref "R4") (pin "2") (pinfunction "2_2") (pintype "passive"))
      (node (ref "SV2") (pin "10") (pinfunction "10_10") (pintype "passive"))
    )
    (net (code "30") (name "LED_GELB") (class "Default")
      (node (ref "R_NULL_2") (pin "2") (pinfunction "2_2") (pintype "passive"))
      (node (ref "SV2") (pin "6") (pinfunction "6_6") (pintype "passive"))
    )
    (net (code "31") (name "LED_GRUEN") (class "Default")
      (node (ref "R_NULL_4") (pin "2") (pinfunction "2_2") (pintype "passive"))
      (node (ref "SV2") (pin "8") (pinfunction "8_8") (pintype "passive"))
    )
    (net (code "32") (name "LED_KICK") (class "Default")
      (node (ref "R_NULL_1") (pin "2") (pinfunction "2_2") (pintype "passive"))
    )
    (net (code "33") (name "LED_ROT") (class "Default")
      (node (ref "R_NULL_3") (pin "2") (pinfunction "2_2") (pintype "passive"))
      (node (ref "SV2") (pin "4") (pinfunction "4_4") (pintype "passive"))
    )
    (net (code "34") (name "MISO") (class "Default")
      (node (ref "U$2") (pin "8") (pinfunction "PB0_8") (pintype "bidirectional"))
      (node (ref "U2") (pin "17") (pinfunction "B3_17") (pintype "bidirectional"))
    )
    (net (code "35") (name "MISO_3V") (class "Default")
      (node (ref "JP1") (pin "3") (pinfunction "3_3") (pintype "passive"))
      (node (ref "U2") (pin "4") (pinfunction "A3_4") (pintype "bidirectional"))
    )
    (net (code "36") (name "MISO_A") (class "Default")
      (node (ref "ISP") (pin "9") (pinfunction "9_9") (pintype "passive"))
      (node (ref "U$2") (pin "1") (pinfunction "(MISO_A)PD2_1") (pintype "bidirectional"))
    )
    (net (code "37") (name "MOSI") (class "Default")
      (node (ref "U$2") (pin "9") (pinfunction "PB1_9") (pintype "bidirectional"))
      (node (ref "U2") (pin "16") (pinfunction "B4_16") (pintype "bidirectional"))
    )
    (net (code "38") (name "MOSI_3V") (class "Default")
      (node (ref "JP1") (pin "2") (pinfunction "2_2") (pintype "passive"))
      (node (ref "U2") (pin "5") (pinfunction "A4_5") (pintype "bidirectional"))
    )
    (net (code "39") (name "MOSI_A") (class "Default")
      (node (ref "ISP") (pin "1") (pinfunction "1_1") (pintype "passive"))
      (node (ref "U$2") (pin "2") (pinfunction "(MOSI_A/TXD)PD3_2") (pintype "bidirectional"))
    )
    (net (code "40") (name "MOTION") (class "Default")
      (node (ref "IC4") (pin "1") (pinfunction "OUT1_1") (pintype "passive"))
      (node (ref "IC4") (pin "5") (pinfunction "OUT2_5") (pintype "passive"))
      (node (ref "P8") (pin "3") (pinfunction "P_3") (pintype "passive"))
      (node (ref "P8") (pin "4") (pinfunction "P_4") (pintype "passive"))
      (node (ref "R15") (pin "1") (pinfunction "1_1") (pintype "passive"))
      (node (ref "R_NULL_4") (pin "1") (pinfunction "1_1") (pintype "passive"))
    )
    (net (code "41") (name "Net-(3V3-PadA)") (class "Default")
      (node (ref "3V3") (pin "A") (pinfunction "A_A") (pintype "passive"))
      (node (ref "R1") (pin "1") (pinfunction "1_1") (pintype "passive"))
    )
    (net (code "42") (name "Net-(5V-PadA)") (class "Default")
      (node (ref "5V") (pin "A") (pinfunction "A_A") (pintype "passive"))
      (node (ref "R18") (pin "1") (pinfunction "1_1") (pintype "passive"))
    )
    (net (code "43") (name "Net-(12V-PadA)") (class "Default")
      (node (ref "12V") (pin "A") (pinfunction "A_A") (pintype "passive"))
      (node (ref "R16") (pin "2") (pinfunction "2_2") (pintype "passive"))
    )
    (net (code "44") (name "Net-(AKKU-PadA)") (class "Default")
      (node (ref "AKKU") (pin "A") (pinfunction "A_A") (pintype "passive"))
      (node (ref "R28") (pin "2") (pinfunction "2_2") (pintype "passive"))
    )
    (net (code "45") (name "Net-(AKT-PadA)") (class "Default")
      (node (ref "AKT") (pin "A") (pinfunction "A_A") (pintype "passive"))
      (node (ref "R17") (pin "2") (pinfunction "2_2") (pintype "passive"))
    )
    (net (code "46") (name "Net-(D1-PadA)") (class "Default")
      (node (ref "D1") (pin "A") (pinfunction "A_A") (pintype "passive"))
      (node (ref "R26") (pin "2") (pinfunction "2_2") (pintype "passive"))
    )
    (net (code "47") (name "Net-(D2-PadA)") (class "Default")
      (node (ref "D2") (pin "A") (pinfunction "A_A") (pintype "passive"))
      (node (ref "R7") (pin "2") (pinfunction "2_2") (pintype "passive"))
    )
    (net (code "48") (name "Net-(D4-C)") (class "Default")
      (node (ref "D4") (pin "3") (pinfunction "C_3") (pintype "passive"))
      (node (ref "R22") (pin "2") (pinfunction "2_2") (pintype "passive"))
      (node (ref "R24") (pin "2") (pinfunction "2_2") (pintype "passive"))
    )
    (net (code "49") (name "Net-(EXT-PadA)") (class "Default")
      (node (ref "EXT") (pin "A") (pinfunction "A_A") (pintype "passive"))
      (node (ref "R25") (pin "2") (pinfunction "2_2") (pintype "passive"))
    )
    (net (code "50") (name "Net-(IC1A--IN)") (class "Default")
      (node (ref "IC1") (pin "2") (pinfunction "-IN_2") (pintype "input"))
      (node (ref "R13") (pin "1") (pinfunction "1_1") (pintype "passive"))
      (node (ref "R21") (pin "2") (pinfunction "2_2") (pintype "passive"))
      (node (ref "R22") (pin "1") (pinfunction "1_1") (pintype "passive"))
    )
    (net (code "51") (name "Net-(IC2-IN)") (class "Default")
      (node (ref "C2") (pin "+") (pinfunction "+_+") (pintype "passive"))
      (node (ref "F1") (pin "2") (pinfunction "2_2") (pintype "passive"))
      (node (ref "IC2") (pin "1") (pinfunction "IN_1") (pintype "input"))
      (node (ref "IC3") (pin "1") (pinfunction "IN_1") (pintype "input"))
    )
    (net (code "52") (name "Net-(IC4-IN)") (class "Default")
      (node (ref "IC4") (pin "2") (pinfunction "IN_2") (pintype "input"))
      (node (ref "VR9") (pin "1") (pinfunction "C_1") (pintype "passive"))
    )
    (net (code "53") (name "Net-(KICK-PadA)") (class "Default")
      (node (ref "KICK") (pin "A") (pinfunction "A_A") (pintype "passive"))
      (node (ref "R23") (pin "2") (pinfunction "2_2") (pintype "passive"))
    )
    (net (code "54") (name "Net-(MOT-PadA)") (class "Default")
      (node (ref "MOT") (pin "A") (pinfunction "A_A") (pintype "passive"))
      (node (ref "R15") (pin "2") (pinfunction "2_2") (pintype "passive"))
    )
    (net (code "55") (name "Net-(Q2-PadG)") (class "Default")
      (node (ref "Q2") (pin "G") (pinfunction "G_G") (pintype "passive"))
      (node (ref "Q3") (pin "G") (pinfunction "G_G") (pintype "passive"))
      (node (ref "Q7") (pin "E") (pinfunction "E_E") (pintype "passive"))
      (node (ref "R34") (pin "2") (pinfunction "2_2") (pintype "passive"))
    )
    (net (code "56") (name "Net-(Q2-PadS)") (class "Default")
      (node (ref "Q2") (pin "S") (pinfunction "S_S") (pintype "passive"))
      (node (ref "Q3") (pin "S") (pinfunction "S_S") (pintype "passive"))
    )
    (net (code "57") (name "Net-(Q4-PadG)") (class "Default")
      (node (ref "Q4") (pin "G") (pinfunction "G_G") (pintype "passive"))
      (node (ref "Q5") (pin "G") (pinfunction "G_G") (pintype "passive"))
      (node (ref "Q6") (pin "E") (pinfunction "E_E") (pintype "passive"))
      (node (ref "R42") (pin "2") (pinfunction "2_2") (pintype "passive"))
    )
    (net (code "58") (name "Net-(Q4-PadS)") (class "Default")
      (node (ref "Q4") (pin "S") (pinfunction "S_S") (pintype "passive"))
      (node (ref "Q5") (pin "S") (pinfunction "S_S") (pintype "passive"))
    )
    (net (code "59") (name "Net-(R6-Pad2)") (class "Default")
      (node (ref "R6") (pin "2") (pinfunction "2_2") (pintype "passive"))
      (node (ref "SJ1") (pin "2") (pinfunction "2_2") (pintype "passive"))
    )
    (net (code "60") (name "Net-(T1-B)") (class "Default")
      (node (ref "R5") (pin "2") (pinfunction "2_2") (pintype "passive"))
      (node (ref "T1") (pin "1") (pinfunction "B_1") (pintype "passive"))
    )
    (net (code "61") (name "Net-(T1-C)") (class "Default")
      (node (ref "D5") (pin "A") (pinfunction "A_A") (pintype "passive"))
      (node (ref "T1") (pin "3") (pinfunction "C_3") (pintype "passive"))
      (node (ref "TDB-05") (pin "-") (pinfunction "2_-") (pintype "passive"))
    )
    (net (code "62") (name "Net-(U$1-RS)") (class "Default")
      (node (ref "R31") (pin "2") (pinfunction "2_2") (pintype "passive"))
      (node (ref "U$1") (pin "8") (pinfunction "RS_8") (pintype "input"))
    )
    (net (code "63") (name "Net-(U$2-AREF)") (class "Default")
      (node (ref "C14") (pin "2") (pinfunction "2_2") (pintype "passive"))
      (node (ref "U$2") (pin "21") (pinfunction "AREF_21") (pintype "bidirectional"))
    )
    (net (code "64") (name "Net-(U$2-PE1(XTAL1))") (class "Default")
      (node (ref "C11") (pin "2") (pinfunction "2_2") (pintype "passive"))
      (node (ref "Q1") (pin "1") (pinfunction "1_1") (pintype "passive"))
      (node (ref "U$2") (pin "10") (pinfunction "PE1(XTAL1)_10") (pintype "bidirectional"))
    )
    (net (code "65") (name "Net-(U$2-PE2(XTAL2))") (class "Default")
      (node (ref "C10") (pin "2") (pinfunction "2_2") (pintype "passive"))
      (node (ref "Q1") (pin "2") (pinfunction "2_2") (pintype "passive"))
      (node (ref "U$2") (pin "11") (pinfunction "PE2(XTAL2)_11") (pintype "bidirectional"))
    )
    (net (code "66") (name "Net-(VR1-C)") (class "Default")
      (node (ref "Q7") (pin "C") (pinfunction "C_C") (pintype "passive"))
      (node (ref "VR1") (pin "1") (pinfunction "C_1") (pintype "passive"))
    )
    (net (code "67") (name "Net-(VR3-C)") (class "Default")
      (node (ref "Q6") (pin "C") (pinfunction "C_C") (pintype "passive"))
      (node (ref "VR3") (pin "1") (pinfunction "C_1") (pintype "passive"))
    )
    (net (code "68") (name "Net-(VR7-C)") (class "Default")
      (node (ref "IC11") (pin "IN") (pinfunction "IN_IN") (pintype "input"))
      (node (ref "VR7") (pin "1") (pinfunction "C_1") (pintype "passive"))
    )
    (net (code "69") (name "Net-(VR8-C)") (class "Default")
      (node (ref "IC12") (pin "IN") (pinfunction "IN_IN") (pintype "input"))
      (node (ref "VR8") (pin "1") (pinfunction "C_1") (pintype "passive"))
    )
    (net (code "70") (name "RST") (class "Default")
      (node (ref "ISP") (pin "5") (pinfunction "5_5") (pintype "passive"))
      (node (ref "U$2") (pin "31") (pinfunction "PE0(RESET)_31") (pintype "input"))
    )
    (net (code "71") (name "RST_ETH") (class "Default")
      (node (ref "U$2") (pin "3") (pinfunction "PC1_3") (pintype "bidirectional"))
      (node (ref "U2") (pin "12") (pinfunction "B8_12") (pintype "bidirectional"))
    )
    (net (code "72") (name "RST_ETH_3V") (class "Default")
      (node (ref "JP2") (pin "3") (pinfunction "3_3") (pintype "passive"))
      (node (ref "U2") (pin "9") (pinfunction "A8_9") (pintype "bidirectional"))
    )
    (net (code "73") (name "RXCAN") (class "Default")
      (node (ref "U$1") (pin "4") (pinfunction "RXD_4") (pintype "output"))
      (node (ref "U$2") (pin "7") (pinfunction "(RXCAN)PC3_7") (pintype "bidirectional"))
    )
    (net (code "74") (name "SCK") (class "Default")
      (node (ref "U$2") (pin "28") (pinfunction "(SCK)PB7_28") (pintype "bidirectional"))
      (node (ref "U2") (pin "15") (pinfunction "B5_15") (pintype "bidirectional"))
    )
    (net (code "75") (name "SCK_3V") (class "Default")
      (node (ref "JP1") (pin "1") (pinfunction "1_1") (pintype "passive"))
      (node (ref "U2") (pin "6") (pinfunction "A5_6") (pintype "bidirectional"))
    )
    (net (code "76") (name "SPEAKER") (class "Default")
      (node (ref "R5") (pin "1") (pinfunction "1_1") (pintype "passive"))
      (node (ref "U$2") (pin "25") (pinfunction "PC7_25") (pintype "bidirectional"))
    )
    (net (code "77") (name "SW_12V") (class "Default")
      (node (ref "D1") (pin "K") (pinfunction "C_K") (pintype "passive"))
      (node (ref "D2") (pin "K") (pinfunction "C_K") (pintype "passive"))
      (node (ref "Q6") (pin "B") (pinfunction "B_B") (pintype "passive"))
      (node (ref "Q7") (pin "B") (pinfunction "B_B") (pintype "passive"))
      (node (ref "SV2") (pin "3") (pinfunction "3_3") (pintype "passive"))
    )
    (net (code "78") (name "SW_AKT") (class "Default")
      (node (ref "SJ2") (pin "1") (pinfunction "1_1") (pintype "passive"))
      (node (ref "SV2") (pin "5") (pinfunction "5_5") (pintype "passive"))
      (node (ref "U$2") (pin "23") (pinfunction "PB3_23") (pintype "bidirectional"))
      (node (ref "VR7") (pin "3") (pinfunction "A_3") (pintype "passive"))
    )
    (net (code "79") (name "SW_BLAU") (class "Default")
      (node (ref "SV2") (pin "9") (pinfunction "9_9") (pintype "passive"))
      (node (ref "U$2") (pin "15") (pinfunction "PD7_15") (pintype "bidirectional"))
    )
    (net (code "80") (name "SW_KICK") (class "Default")
      (node (ref "SJ2") (pin "2") (pinfunction "2_2") (pintype "passive"))
      (node (ref "VR8") (pin "3") (pinfunction "A_3") (pintype "passive"))
    )
    (net (code "81") (name "SW_MOT") (class "Default")
      (node (ref "SV2") (pin "7") (pinfunction "7_7") (pintype "passive"))
      (node (ref "U$2") (pin "24") (pinfunction "PB4_24") (pintype "bidirectional"))
      (node (ref "VR9") (pin "3") (pinfunction "A_3") (pintype "passive"))
    )
    (net (code "82") (name "TXCAN") (class "Default")
      (node (ref "U$1") (pin "1") (pinfunction "TXD_1") (pintype "input"))
      (node (ref "U$2") (pin "6") (pinfunction "(TXCAN)PC2_6") (pintype "bidirectional"))
    )
    (net (code "83") (name "WOL_ETH") (class "Default")
      (node (ref "U$2") (pin "29") (pinfunction "PD0_29") (pintype "bidirectional"))
      (node (ref "U2") (pin "18") (pinfunction "B2_18") (pintype "bidirectional"))
    )
    (net (code "84") (name "WOL_ETH_3V") (class "Default")
      (node (ref "JP1") (pin "4") (pinfunction "4_4") (pintype "passive"))
      (node (ref "U2") (pin "3") (pinfunction "A2_3") (pintype "bidirectional"))
    )
    (net (code "85") (name "unconnected-(ISP-Pad3)") (class "Default")
      (node (ref "ISP") (pin "3") (pinfunction "3_3") (pintype "passive"))
    )
    (net (code "86") (name "unconnected-(RJ_2-PadP$4)") (class "Default")
      (node (ref "RJ_2") (pin "P$4") (pinfunction "P$4_P$4") (pintype "bidirectional"))
    )
    (net (code "87") (name "unconnected-(U$1-VREF-Pad5)") (class "Default")
      (node (ref "U$1") (pin "5") (pinfunction "VREF_5") (pintype "output"))
    )
    (net (code "88") (name "unconnected-(U$2-PC6-Pad22)") (class "Default")
      (node (ref "U$2") (pin "22") (pinfunction "PC6_22") (pintype "bidirectional"))
    )
  )
)
